# ezo_probe_expansion_3_1.net
KiCad netlist of a schematic drawn in EAGLE
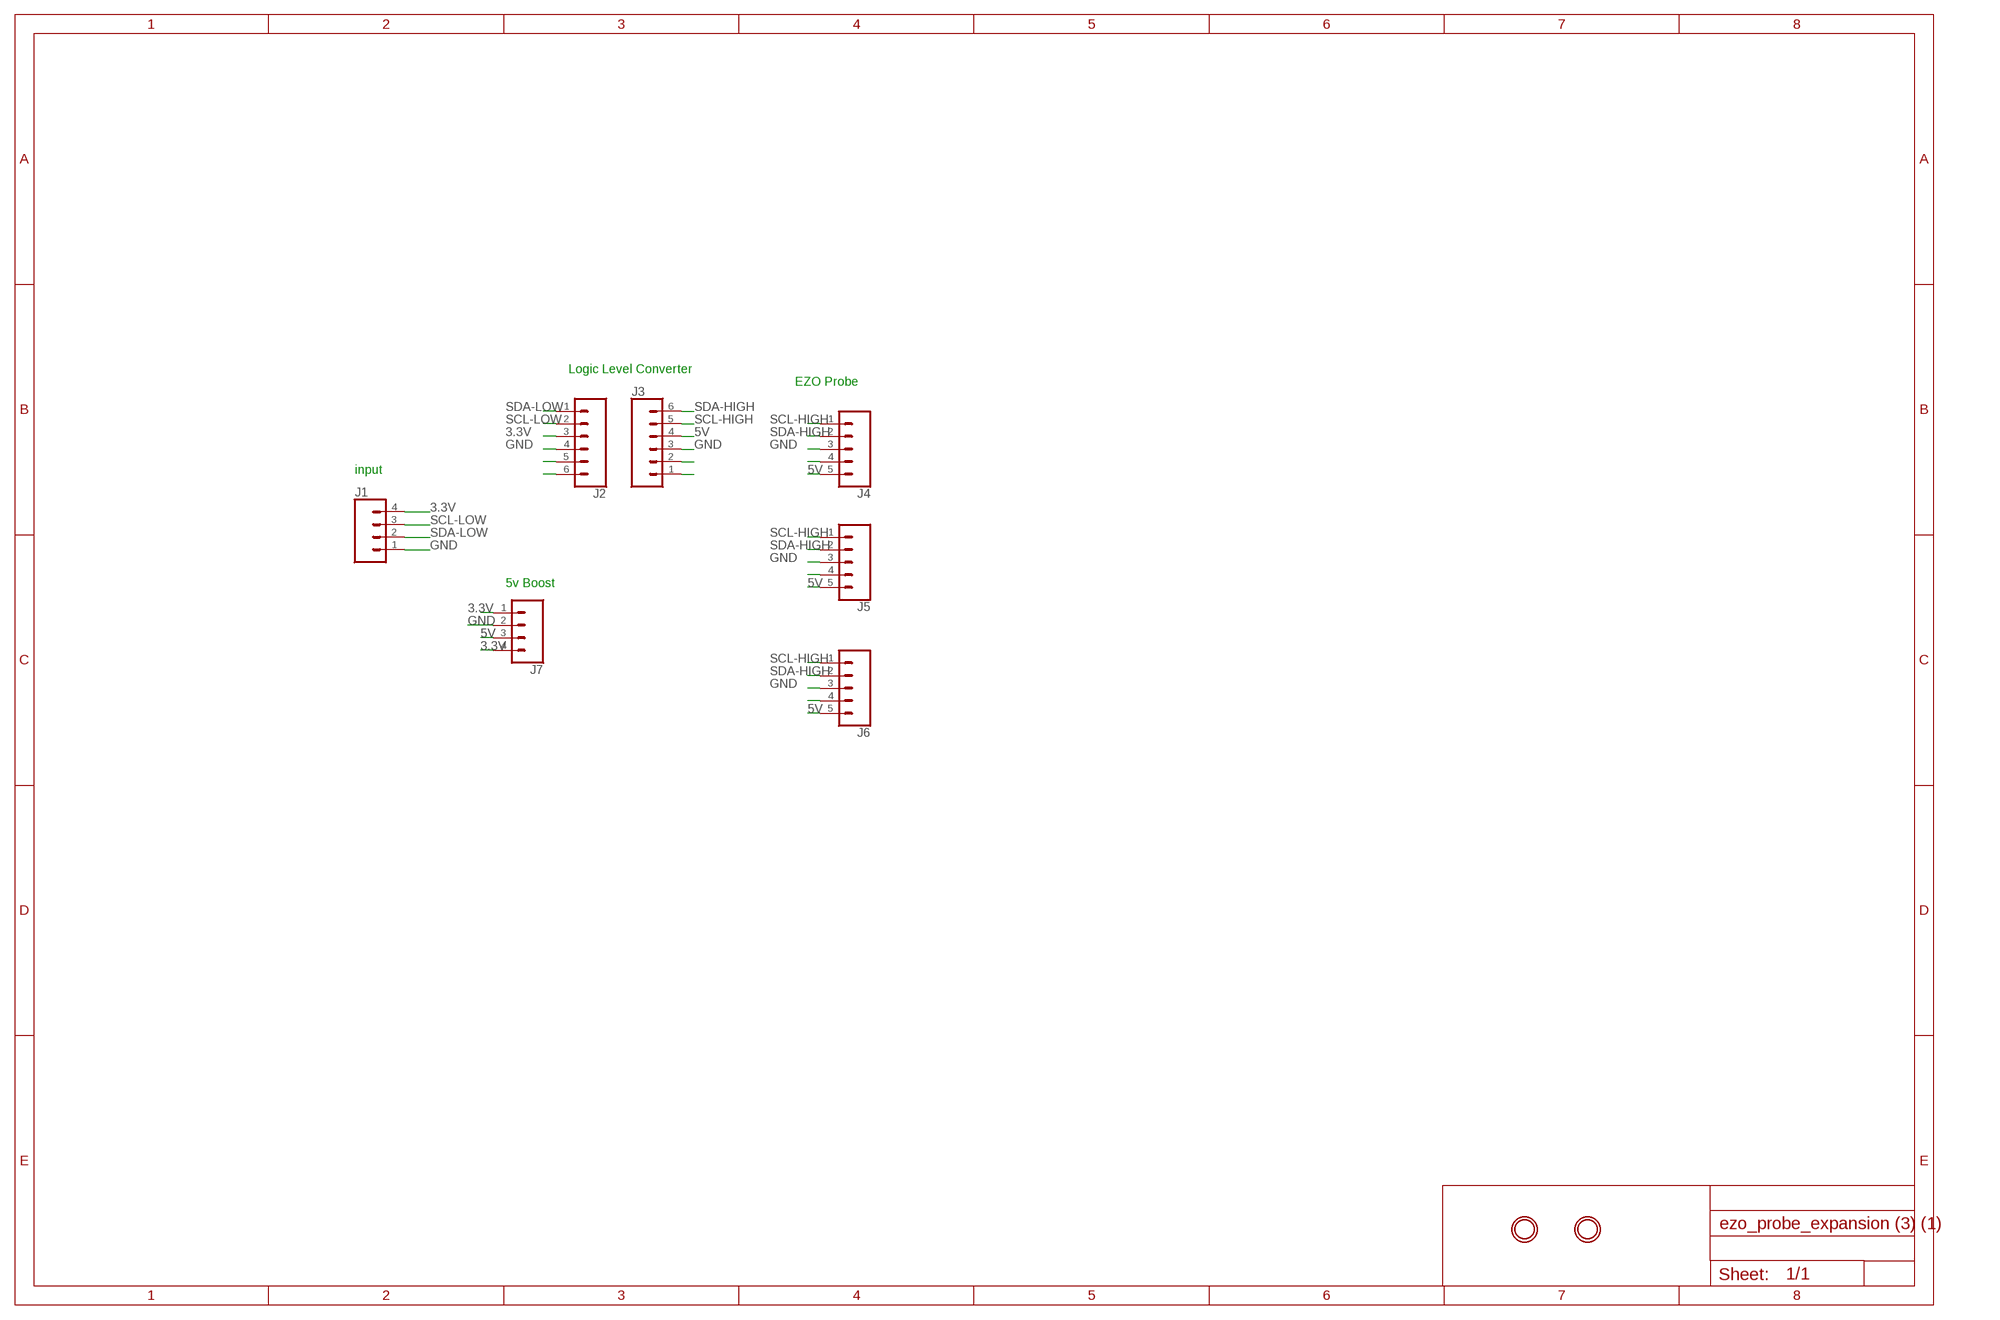
[diagram p0: schematic, sheet 1]

(export (version "E")
  (design (tool "Eeschema 10.0.6"))
  (components
    (comp (ref "J1")
      (value "CONN_04PTH")
      (footprint "eagle-import:1X04")
      (libsource (lib "eagle-import") (part "CONN_04PTH"))
    )
    (comp (ref "J2")
      (value "CONN_06SILK_FEMALE_PTH")
      (footprint "eagle-import:1X06")
      (libsource (lib "eagle-import") (part "CONN_06SILK_FEMALE_PTH"))
    )
    (comp (ref "J3")
      (value "CONN_06SILK_FEMALE_PTH")
      (footprint "eagle-import:1X06")
      (libsource (lib "eagle-import") (part "CONN_06SILK_FEMALE_PTH"))
    )
    (comp (ref "J4")
      (value "CONN_05PTH")
      (footprint "eagle-import:1X05")
      (libsource (lib "eagle-import") (part "CONN_05PTH"))
    )
    (comp (ref "J5")
      (value "CONN_05PTH")
      (footprint "eagle-import:1X05")
      (libsource (lib "eagle-import") (part "CONN_05PTH"))
    )
    (comp (ref "J6")
      (value "CONN_05PTH")
      (footprint "eagle-import:1X05")
      (libsource (lib "eagle-import") (part "CONN_05PTH"))
    )
    (comp (ref "J7")
      (value "CONN_04PTH")
      (footprint "eagle-import:1X04")
      (libsource (lib "eagle-import") (part "CONN_04PTH"))
    )
    (comp (ref "U$1")
      (value "MOUNTINGHOLE2.5")
      (footprint "eagle-import:MOUNTINGHOLE_2.5_PLATED")
      (libsource (lib "eagle-import") (part "MOUNTINGHOLE2.5"))
    )
    (comp (ref "U$2")
      (value "MOUNTINGHOLE2.5")
      (footprint "eagle-import:MOUNTINGHOLE_2.5_PLATED")
      (libsource (lib "eagle-import") (part "MOUNTINGHOLE2.5"))
    )
  )
  (nets
    (net (code "1") (name "/3.3V") (class "Default")
      (node (ref "J1") (pin "4") (pinfunction "4_4") (pintype "passive"))
      (node (ref "J2") (pin "3") (pinfunction "3_3") (pintype "passive"))
      (node (ref "J7") (pin "1") (pinfunction "1_1") (pintype "passive"))
      (node (ref "J7") (pin "4") (pinfunction "4_4") (pintype "passive"))
    )
    (net (code "2") (name "/5V") (class "Default")
      (node (ref "J3") (pin "4") (pinfunction "4_4") (pintype "passive"))
      (node (ref "J4") (pin "5") (pinfunction "5_5") (pintype "passive"))
      (node (ref "J5") (pin "5") (pinfunction "5_5") (pintype "passive"))
      (node (ref "J6") (pin "5") (pinfunction "5_5") (pintype "passive"))
      (node (ref "J7") (pin "3") (pinfunction "3_3") (pintype "passive"))
    )
    (net (code "3") (name "/GND") (class "Default")
      (node (ref "J1") (pin "1") (pinfunction "1_1") (pintype "passive"))
      (node (ref "J2") (pin "4") (pinfunction "4_4") (pintype "passive"))
      (node (ref "J3") (pin "3") (pinfunction "3_3") (pintype "passive"))
      (node (ref "J4") (pin "3") (pinfunction "3_3") (pintype "passive"))
      (node (ref "J5") (pin "3") (pinfunction "3_3") (pintype "passive"))
      (node (ref "J6") (pin "3") (pinfunction "3_3") (pintype "passive"))
      (node (ref "J7") (pin "2") (pinfunction "2_2") (pintype "passive"))
    )
    (net (code "4") (name "/SCL-HIGH") (class "Default")
      (node (ref "J3") (pin "5") (pinfunction "5_5") (pintype "passive"))
      (node (ref "J4") (pin "1") (pinfunction "1_1") (pintype "passive"))
      (node (ref "J5") (pin "1") (pinfunction "1_1") (pintype "passive"))
      (node (ref "J6") (pin "1") (pinfunction "1_1") (pintype "passive"))
    )
    (net (code "5") (name "/SCL-LOW") (class "Default")
      (node (ref "J1") (pin "3") (pinfunction "3_3") (pintype "passive"))
      (node (ref "J2") (pin "2") (pinfunction "2_2") (pintype "passive"))
    )
    (net (code "6") (name "/SDA-HIGH") (class "Default")
      (node (ref "J3") (pin "6") (pinfunction "6_6") (pintype "passive"))
      (node (ref "J4") (pin "2") (pinfunction "2_2") (pintype "passive"))
      (node (ref "J5") (pin "2") (pinfunction "2_2") (pintype "passive"))
      (node (ref "J6") (pin "2") (pinfunction "2_2") (pintype "passive"))
    )
    (net (code "7") (name "/SDA-LOW") (class "Default")
      (node (ref "J1") (pin "2") (pinfunction "2_2") (pintype "passive"))
      (node (ref "J2") (pin "1") (pinfunction "1_1") (pintype "passive"))
    )
    (net (code "8") (name "unconnected-(J2-Pad5)") (class "Default")
      (node (ref "J2") (pin "5") (pinfunction "5_5") (pintype "passive"))
    )
    (net (code "9") (name "unconnected-(J2-Pad6)") (class "Default")
      (node (ref "J2") (pin "6") (pinfunction "6_6") (pintype "passive"))
    )
    (net (code "10") (name "unconnected-(J3-Pad1)") (class "Default")
      (node (ref "J3") (pin "1") (pinfunction "1_1") (pintype "passive"))
    )
    (net (code "11") (name "unconnected-(J3-Pad2)") (class "Default")
      (node (ref "J3") (pin "2") (pinfunction "2_2") (pintype "passive"))
    )
    (net (code "12") (name "unconnected-(J4-Pad4)") (class "Default")
      (node (ref "J4") (pin "4") (pinfunction "4_4") (pintype "passive"))
    )
    (net (code "13") (name "unconnected-(J5-Pad4)") (class "Default")
      (node (ref "J5") (pin "4") (pinfunction "4_4") (pintype "passive"))
    )
    (net (code "14") (name "unconnected-(J6-Pad4)") (class "Default")
      (node (ref "J6") (pin "4") (pinfunction "4_4") (pintype "passive"))
    )
  )
)
